# geiger.net
KiCad netlist of a schematic drawn in EAGLE
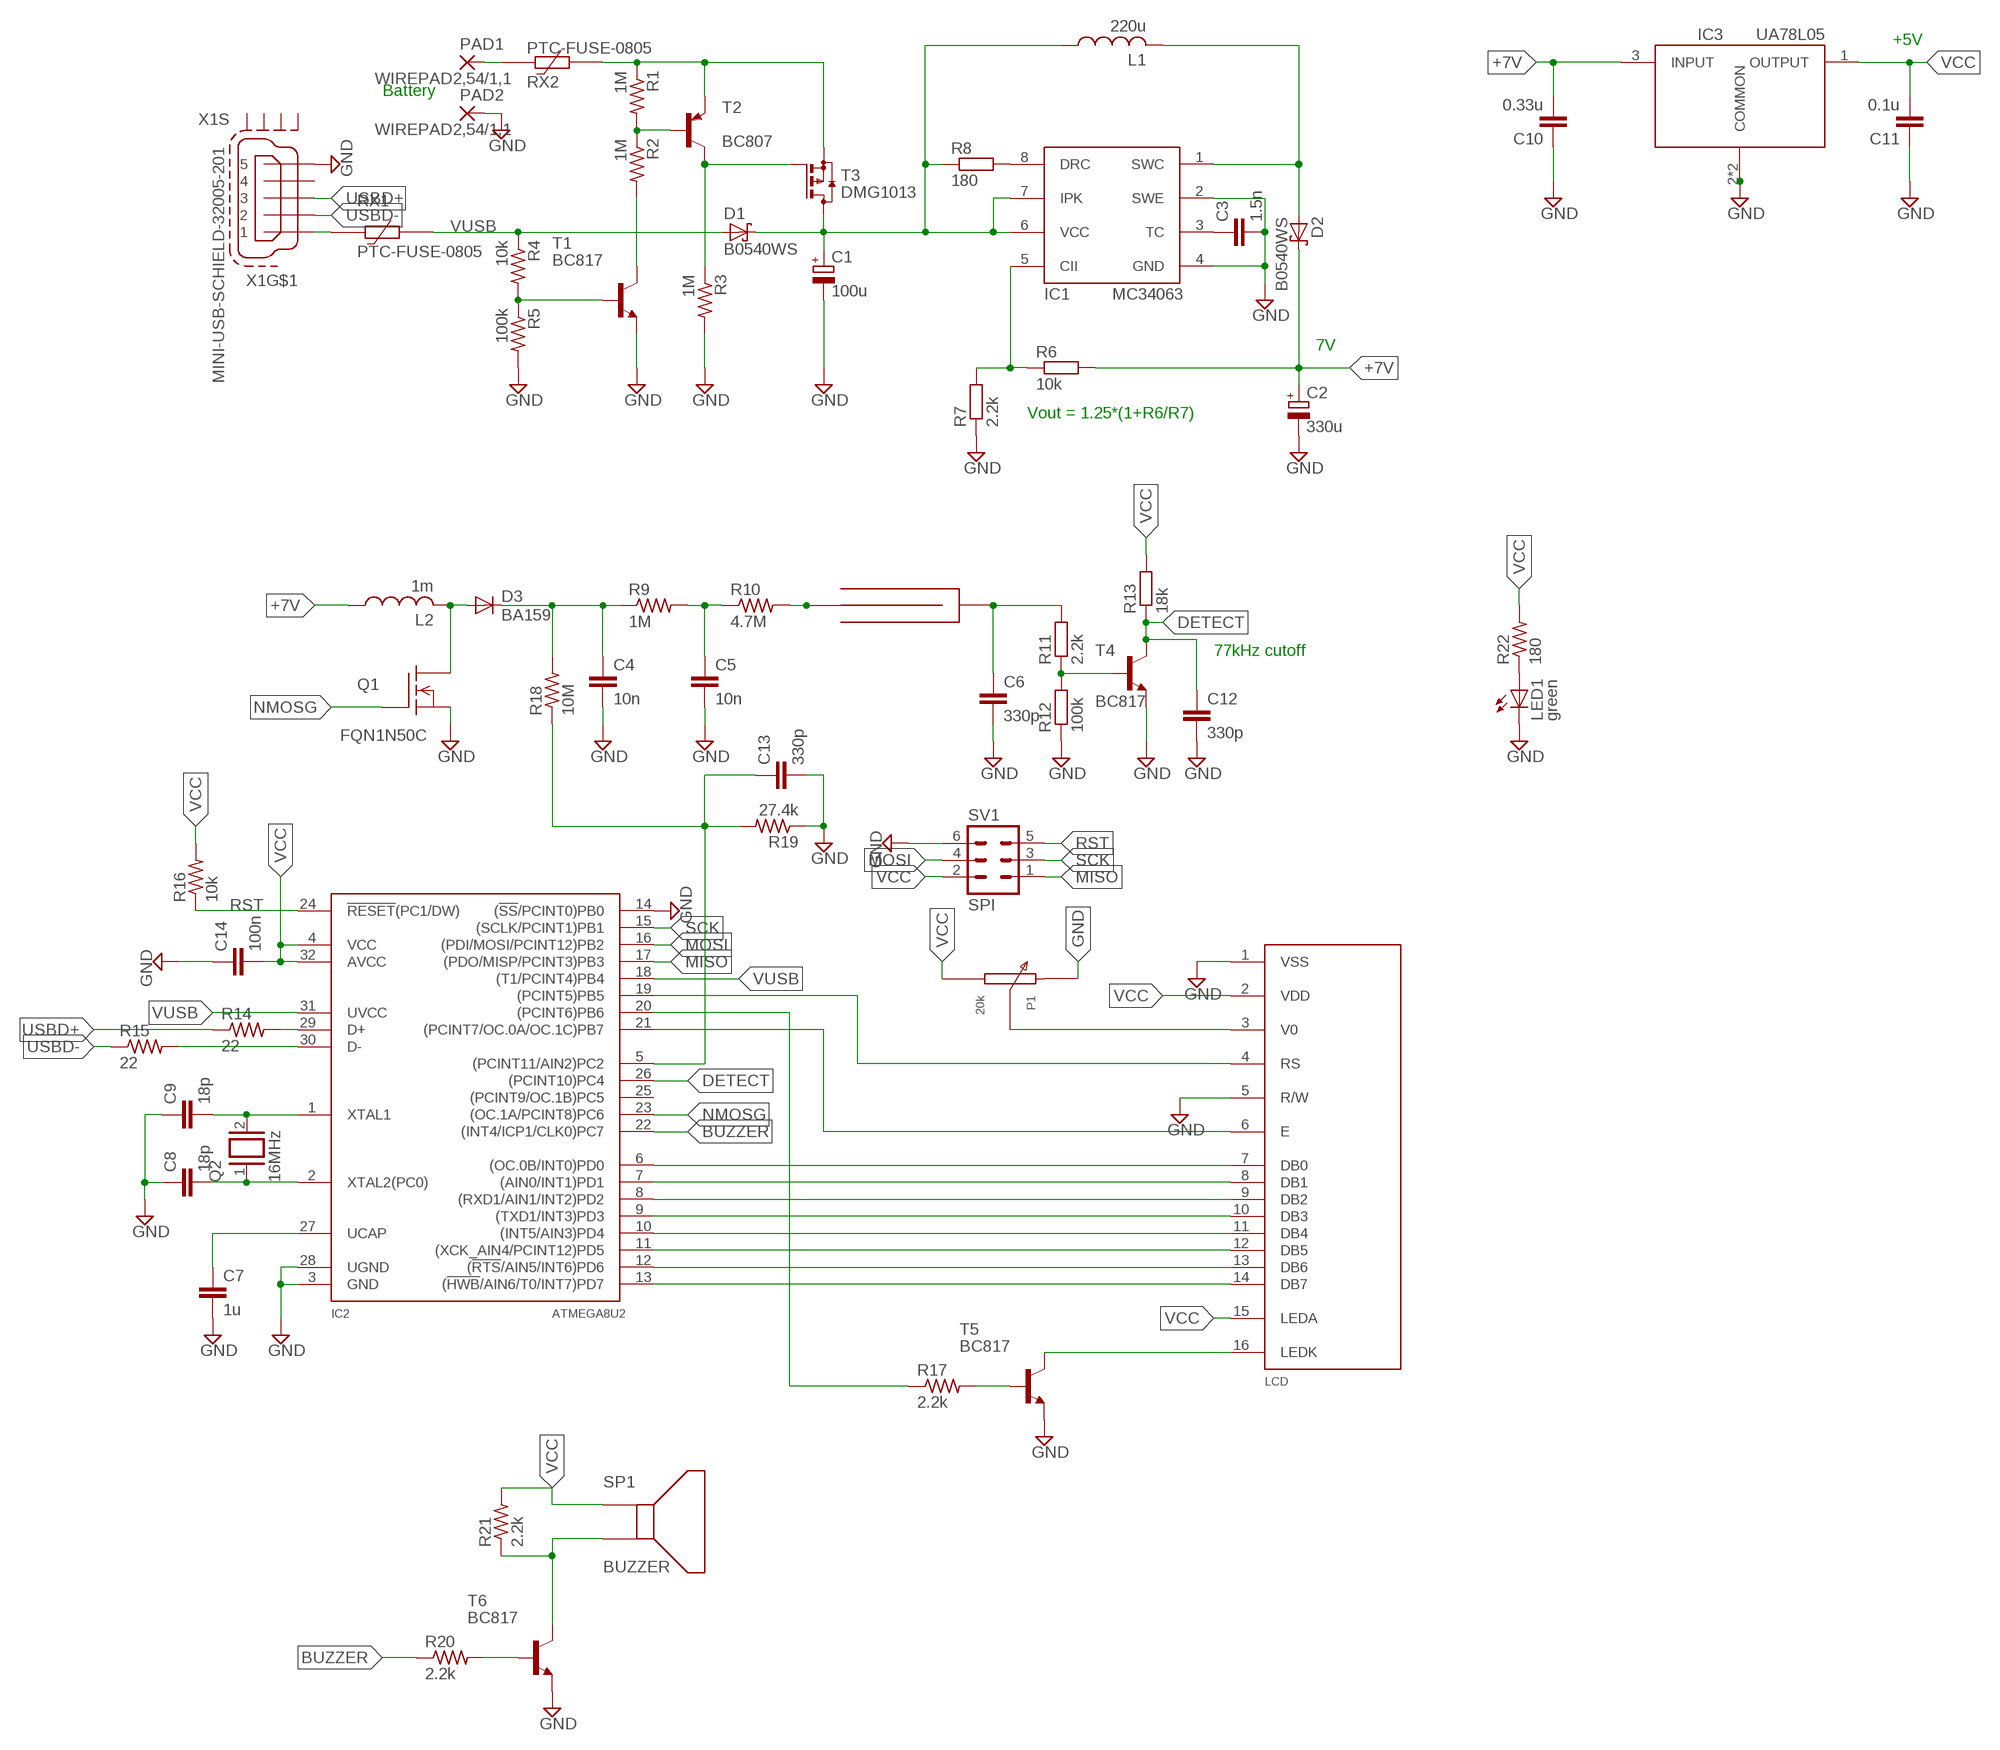
[diagram p0: schematic, sheet 1]

(export (version "E")
  (design (tool "Eeschema 10.0.6"))
  (components
    (comp (ref "C1")
      (value "100u")
      (footprint "eagle-import:E2,5-6")
      (libsource (lib "eagle-import") (part "CPOL-EUE2.5-6"))
    )
    (comp (ref "C2")
      (value "330u")
      (footprint "eagle-import:E2,5-6")
      (libsource (lib "eagle-import") (part "CPOL-EUE2.5-6"))
    )
    (comp (ref "C3")
      (value "1.5n")
      (footprint "eagle-import:C0603")
      (libsource (lib "eagle-import") (part "C-EUC0603"))
    )
    (comp (ref "C4")
      (value "10n")
      (footprint "eagle-import:C050-024X044")
      (libsource (lib "eagle-import") (part "C-EU050-024X044"))
    )
    (comp (ref "C5")
      (value "10n")
      (footprint "eagle-import:C050-024X044")
      (libsource (lib "eagle-import") (part "C-EU050-024X044"))
    )
    (comp (ref "C6")
      (value "330p")
      (footprint "eagle-import:C0603")
      (libsource (lib "eagle-import") (part "C-EUC0603"))
    )
    (comp (ref "C7")
      (value "1u")
      (footprint "eagle-import:C0603")
      (libsource (lib "eagle-import") (part "C-EUC0603"))
    )
    (comp (ref "C8")
      (value "18p")
      (footprint "eagle-import:C0603")
      (libsource (lib "eagle-import") (part "C-EUC0603"))
    )
    (comp (ref "C9")
      (value "18p")
      (footprint "eagle-import:C0603")
      (libsource (lib "eagle-import") (part "C-EUC0603"))
    )
    (comp (ref "C10")
      (value "0.33u")
      (footprint "eagle-import:C0603")
      (libsource (lib "eagle-import") (part "C-EUC0603"))
    )
    (comp (ref "C11")
      (value "0.1u")
      (footprint "eagle-import:C0603")
      (libsource (lib "eagle-import") (part "C-EUC0603"))
    )
    (comp (ref "C12")
      (value "330p")
      (footprint "eagle-import:C0603")
      (libsource (lib "eagle-import") (part "C-EUC0603"))
    )
    (comp (ref "C13")
      (value "330p")
      (footprint "eagle-import:C0603")
      (libsource (lib "eagle-import") (part "C-EUC0603"))
    )
    (comp (ref "C14")
      (value "100n")
      (footprint "eagle-import:C0603")
      (libsource (lib "eagle-import") (part "C-EUC0603"))
    )
    (comp (ref "D1")
      (value "B0540WS")
      (footprint "eagle-import:SOD323-R")
      (libsource (lib "eagle-import") (part "B0540WS"))
    )
    (comp (ref "D2")
      (value "B0540WS")
      (footprint "eagle-import:SOD323-R")
      (libsource (lib "eagle-import") (part "B0540WS"))
    )
    (comp (ref "D3")
      (value "BA159")
      (footprint "eagle-import:DO41-10")
      (libsource (lib "eagle-import") (part "BA159"))
    )
    (comp (ref "G1")
      (value "CI-22BG/SI-3BG")
      (footprint "eagle-import:FUSE102074")
      (libsource (lib "eagle-import") (part "CI-22BG/SI-3BG"))
    )
    (comp (ref "IC1")
      (value "MC34063")
      (footprint "eagle-import:SO8")
      (libsource (lib "eagle-import") (part "MC34063"))
    )
    (comp (ref "IC2")
      (value "ATMEGA8U2")
      (footprint "eagle-import:TQFP32-08")
      (libsource (lib "eagle-import") (part "ATMEGA8U2"))
    )
    (comp (ref "IC3")
      (value "UA78L05")
      (footprint "eagle-import:SOT89")
      (libsource (lib "eagle-import") (part "UA78L05"))
    )
    (comp (ref "L1")
      (value "220u")
      (footprint "eagle-import:L8012")
      (libsource (lib "eagle-import") (part "BOURNS8012"))
    )
    (comp (ref "L2")
      (value "1m")
      (footprint "eagle-import:L8012")
      (libsource (lib "eagle-import") (part "BOURNS8012"))
    )
    (comp (ref "LCD")
      (value "TAYDA-LCD")
      (footprint "eagle-import:LCD-PINOUT")
      (libsource (lib "eagle-import") (part "TAYDA-LCD"))
    )
    (comp (ref "LED1")
      (value "green")
      (footprint "eagle-import:CHIP-LED0603")
      (libsource (lib "eagle-import") (part "LEDCHIP-LED0603"))
    )
    (comp (ref "P1")
      (value "20k")
      (footprint "eagle-import:TRIMPOT")
      (libsource (lib "eagle-import") (part "TRIMPOT"))
    )
    (comp (ref "PAD1")
      (value "WIREPAD2,54/1,1")
      (footprint "eagle-import:2,54_1,1")
      (libsource (lib "eagle-import") (part "WIREPAD2,54/1,1"))
    )
    (comp (ref "PAD2")
      (value "WIREPAD2,54/1,1")
      (footprint "eagle-import:2,54_1,1")
      (libsource (lib "eagle-import") (part "WIREPAD2,54/1,1"))
    )
    (comp (ref "Q1")
      (value "FQN1N50C")
      (footprint "eagle-import:TO92")
      (libsource (lib "eagle-import") (part "FQN1N50C"))
    )
    (comp (ref "Q2")
      (value "16MHz")
      (footprint "eagle-import:QS")
      (libsource (lib "eagle-import") (part "XTAL/S"))
    )
    (comp (ref "R1")
      (value "1M")
      (footprint "eagle-import:R0603")
      (libsource (lib "eagle-import") (part "resistor_R-US_R0603"))
    )
    (comp (ref "R2")
      (value "1M")
      (footprint "eagle-import:R0603")
      (libsource (lib "eagle-import") (part "resistor_R-US_R0603"))
    )
    (comp (ref "R3")
      (value "1M")
      (footprint "eagle-import:R0603")
      (libsource (lib "eagle-import") (part "resistor_R-US_R0603"))
    )
    (comp (ref "R4")
      (value "10k")
      (footprint "eagle-import:R0603")
      (libsource (lib "eagle-import") (part "resistor_R-US_R0603"))
    )
    (comp (ref "R5")
      (value "100k")
      (footprint "eagle-import:R0603")
      (libsource (lib "eagle-import") (part "resistor_R-US_R0603"))
    )
    (comp (ref "R6")
      (value "10k")
      (footprint "eagle-import:R0603")
      (libsource (lib "eagle-import") (part "R-EU_R0603"))
    )
    (comp (ref "R7")
      (value "2.2k")
      (footprint "eagle-import:R0603")
      (libsource (lib "eagle-import") (part "R-EU_R0603"))
    )
    (comp (ref "R8")
      (value "180")
      (footprint "eagle-import:R0603")
      (libsource (lib "eagle-import") (part "R-EU_R0603"))
    )
    (comp (ref "R9")
      (value "1M")
      (footprint "eagle-import:0207_7")
      (libsource (lib "eagle-import") (part "R-US_0207/7"))
    )
    (comp (ref "R10")
      (value "4.7M")
      (footprint "eagle-import:0207_7")
      (libsource (lib "eagle-import") (part "R-US_0207/7"))
    )
    (comp (ref "R11")
      (value "2.2k")
      (footprint "eagle-import:R0603")
      (libsource (lib "eagle-import") (part "R-EU_R0603"))
    )
    (comp (ref "R12")
      (value "100k")
      (footprint "eagle-import:R0603")
      (libsource (lib "eagle-import") (part "R-EU_R0603"))
    )
    (comp (ref "R13")
      (value "18k")
      (footprint "eagle-import:R0603")
      (libsource (lib "eagle-import") (part "R-EU_R0603"))
    )
    (comp (ref "R14")
      (value "22")
      (footprint "eagle-import:R0603")
      (libsource (lib "eagle-import") (part "resistor_R-US_R0603"))
    )
    (comp (ref "R15")
      (value "22")
      (footprint "eagle-import:R0603")
      (libsource (lib "eagle-import") (part "resistor_R-US_R0603"))
    )
    (comp (ref "R16")
      (value "10k")
      (footprint "eagle-import:R0603")
      (libsource (lib "eagle-import") (part "resistor_R-US_R0603"))
    )
    (comp (ref "R17")
      (value "2.2k")
      (footprint "eagle-import:R0603")
      (libsource (lib "eagle-import") (part "resistor_R-US_R0603"))
    )
    (comp (ref "R18")
      (value "10M")
      (footprint "eagle-import:0207_7")
      (libsource (lib "eagle-import") (part "R-US_0207/7"))
    )
    (comp (ref "R19")
      (value "27.4k")
      (footprint "eagle-import:R0603")
      (libsource (lib "eagle-import") (part "resistor_R-US_R0603"))
    )
    (comp (ref "R20")
      (value "2.2k")
      (footprint "eagle-import:R0603")
      (libsource (lib "eagle-import") (part "resistor_R-US_R0603"))
    )
    (comp (ref "R21")
      (value "2.2k")
      (footprint "eagle-import:R0603")
      (libsource (lib "eagle-import") (part "resistor_R-US_R0603"))
    )
    (comp (ref "R22")
      (value "180")
      (footprint "eagle-import:R0603")
      (libsource (lib "eagle-import") (part "resistor_R-US_R0603"))
    )
    (comp (ref "RX1")
      (value "PTC-FUSE-0805")
      (footprint "eagle-import:R0805")
      (libsource (lib "eagle-import") (part "PTC-FUSE-0805"))
    )
    (comp (ref "RX2")
      (value "PTC-FUSE-0805")
      (footprint "eagle-import:R0805")
      (libsource (lib "eagle-import") (part "PTC-FUSE-0805"))
    )
    (comp (ref "SP1")
      (value "BUZZER")
      (footprint "eagle-import:BUZZER")
      (libsource (lib "eagle-import") (part "BUZZER"))
    )
    (comp (ref "SV1")
      (value "SPI")
      (footprint "eagle-import:MA03-2")
      (libsource (lib "eagle-import") (part "MA03-2"))
    )
    (comp (ref "T1")
      (value "BC817")
      (footprint "eagle-import:SOT23-BEC")
      (libsource (lib "eagle-import") (part "-NPN-SOT23-BECBC817-40"))
    )
    (comp (ref "T2")
      (value "BC807")
      (footprint "eagle-import:SOT23-BEC")
      (libsource (lib "eagle-import") (part "-PNP-SOT23-BECBC807-40"))
    )
    (comp (ref "T3")
      (value "DMG1013")
      (footprint "eagle-import:SOT323")
      (libsource (lib "eagle-import") (part "DMG1013"))
    )
    (comp (ref "T4")
      (value "BC817")
      (footprint "eagle-import:SOT23-BEC")
      (libsource (lib "eagle-import") (part "-NPN-SOT23-BECBC817-40"))
    )
    (comp (ref "T5")
      (value "BC817")
      (footprint "eagle-import:SOT23-BEC")
      (libsource (lib "eagle-import") (part "-NPN-SOT23-BECBC817-40"))
    )
    (comp (ref "T6")
      (value "BC817")
      (footprint "eagle-import:SOT23-BEC")
      (libsource (lib "eagle-import") (part "-NPN-SOT23-BECBC817-40"))
    )
    (comp (ref "X1")
      (value "MINI-USB-SCHIELD-32005-201")
      (footprint "eagle-import:32005-201")
      (libsource (lib "eagle-import") (part "MINI-USB-SCHIELD-32005-201"))
    )
  )
  (nets
    (net (code "1") (name "+7V") (class "Default")
      (node (ref "C10") (pin "2") (pinfunction "2_2") (pintype "passive"))
      (node (ref "C2") (pin "+") (pinfunction "+_+") (pintype "passive"))
      (node (ref "D2") (pin "C") (pinfunction "C_C") (pintype "passive"))
      (node (ref "IC3") (pin "3") (pinfunction "INPUT_3") (pintype "bidirectional"))
      (node (ref "L2") (pin "1") (pinfunction "1_1") (pintype "passive"))
      (node (ref "R6") (pin "2") (pinfunction "2_2") (pintype "passive"))
    )
    (net (code "2") (name "BUZZER") (class "Default")
      (node (ref "IC2") (pin "22") (pinfunction "(INT4/ICP1/CLK0)PC7_22") (pintype "bidirectional"))
      (node (ref "R20") (pin "1") (pinfunction "1_1") (pintype "passive"))
    )
    (net (code "3") (name "DETECT") (class "Default")
      (node (ref "C12") (pin "1") (pinfunction "1_1") (pintype "passive"))
      (node (ref "IC2") (pin "26") (pinfunction "(PCINT10)PC4_26") (pintype "bidirectional"))
      (node (ref "R13") (pin "1") (pinfunction "1_1") (pintype "passive"))
      (node (ref "T4") (pin "C") (pinfunction "C_C") (pintype "passive"))
    )
    (net (code "4") (name "GND") (class "Default")
      (node (ref "C1") (pin "-") (pinfunction "-_-") (pintype "passive"))
      (node (ref "C10") (pin "1") (pinfunction "1_1") (pintype "passive"))
      (node (ref "C11") (pin "1") (pinfunction "1_1") (pintype "passive"))
      (node (ref "C12") (pin "2") (pinfunction "2_2") (pintype "passive"))
      (node (ref "C13") (pin "2") (pinfunction "2_2") (pintype "passive"))
      (node (ref "C14") (pin "1") (pinfunction "1_1") (pintype "passive"))
      (node (ref "C2") (pin "-") (pinfunction "-_-") (pintype "passive"))
      (node (ref "C3") (pin "2") (pinfunction "2_2") (pintype "passive"))
      (node (ref "C4") (pin "2") (pinfunction "2_2") (pintype "passive"))
      (node (ref "C5") (pin "2") (pinfunction "2_2") (pintype "passive"))
      (node (ref "C6") (pin "2") (pinfunction "2_2") (pintype "passive"))
      (node (ref "C7") (pin "2") (pinfunction "2_2") (pintype "passive"))
      (node (ref "C8") (pin "1") (pinfunction "1_1") (pintype "passive"))
      (node (ref "C9") (pin "1") (pinfunction "1_1") (pintype "passive"))
      (node (ref "IC1") (pin "2") (pinfunction "SWE_2") (pintype "bidirectional"))
      (node (ref "IC1") (pin "4") (pinfunction "GND_4") (pintype "bidirectional"))
      (node (ref "IC2") (pin "14") (pinfunction "(~{SS}/PCINT0)PB0_14") (pintype "bidirectional"))
      (node (ref "IC2") (pin "28") (pinfunction "UGND_28") (pintype "bidirectional"))
      (node (ref "IC2") (pin "3") (pinfunction "GND_3") (pintype "bidirectional"))
      (node (ref "IC3") (pin "2") (pinfunction "COMMON_2") (pintype "bidirectional"))
      (node (ref "IC3") (pin "2@1") (pinfunction "COMMON_2@1") (pintype "bidirectional"))
      (node (ref "LCD") (pin "1") (pinfunction "VSS_1") (pintype "bidirectional"))
      (node (ref "LCD") (pin "5") (pinfunction "R/W_5") (pintype "bidirectional"))
      (node (ref "LED1") (pin "C") (pinfunction "C_C") (pintype "passive"))
      (node (ref "P1") (pin "P$2") (pinfunction "1_P$2") (pintype "bidirectional"))
      (node (ref "PAD2") (pin "1") (pinfunction "P_1") (pintype "passive"))
      (node (ref "Q1") (pin "1") (pinfunction "S_1") (pintype "passive"))
      (node (ref "R12") (pin "1") (pinfunction "1_1") (pintype "passive"))
      (node (ref "R19") (pin "1") (pinfunction "1_1") (pintype "passive"))
      (node (ref "R3") (pin "2") (pinfunction "2_2") (pintype "passive"))
      (node (ref "R5") (pin "2") (pinfunction "2_2") (pintype "passive"))
      (node (ref "R7") (pin "1") (pinfunction "1_1") (pintype "passive"))
      (node (ref "SV1") (pin "6") (pinfunction "6_6") (pintype "passive"))
      (node (ref "T1") (pin "E") (pinfunction "E_E") (pintype "passive"))
      (node (ref "T4") (pin "E") (pinfunction "E_E") (pintype "passive"))
      (node (ref "T5") (pin "E") (pinfunction "E_E") (pintype "passive"))
      (node (ref "T6") (pin "E") (pinfunction "E_E") (pintype "passive"))
      (node (ref "X1") (pin "5") (pinfunction "5_5") (pintype "passive"))
    )
    (net (code "5") (name "MISO") (class "Default")
      (node (ref "IC2") (pin "17") (pinfunction "(PDO/MISP/PCINT3)PB3_17") (pintype "bidirectional"))
      (node (ref "SV1") (pin "1") (pinfunction "1_1") (pintype "passive"))
    )
    (net (code "6") (name "MOSI") (class "Default")
      (node (ref "IC2") (pin "16") (pinfunction "(PDI/MOSI/PCINT12)PB2_16") (pintype "bidirectional"))
      (node (ref "SV1") (pin "4") (pinfunction "4_4") (pintype "passive"))
    )
    (net (code "7") (name "NMOSG") (class "Default")
      (node (ref "IC2") (pin "23") (pinfunction "(OC.1A/PCINT8)PC6_23") (pintype "bidirectional"))
      (node (ref "Q1") (pin "3") (pinfunction "G_3") (pintype "passive"))
    )
    (net (code "8") (name "Net-(C4-Pad1)") (class "Default")
      (node (ref "C4") (pin "1") (pinfunction "1_1") (pintype "passive"))
      (node (ref "D3") (pin "C") (pinfunction "C_C") (pintype "passive"))
      (node (ref "R18") (pin "2") (pinfunction "2_2") (pintype "passive"))
      (node (ref "R9") (pin "1") (pinfunction "1_1") (pintype "passive"))
    )
    (net (code "9") (name "Net-(C5-Pad1)") (class "Default")
      (node (ref "C5") (pin "1") (pinfunction "1_1") (pintype "passive"))
      (node (ref "R10") (pin "1") (pinfunction "1_1") (pintype "passive"))
      (node (ref "R9") (pin "2") (pinfunction "2_2") (pintype "passive"))
    )
    (net (code "10") (name "Net-(C6-Pad1)") (class "Default")
      (node (ref "C6") (pin "1") (pinfunction "1_1") (pintype "passive"))
      (node (ref "G1") (pin "C1") (pinfunction "C_C1") (pintype "bidirectional"))
      (node (ref "G1") (pin "C2") (pinfunction "C_C2") (pintype "bidirectional"))
      (node (ref "G1") (pin "C3") (pinfunction "C_C3") (pintype "bidirectional"))
      (node (ref "G1") (pin "C4") (pinfunction "C_C4") (pintype "bidirectional"))
      (node (ref "R11") (pin "2") (pinfunction "2_2") (pintype "passive"))
    )
    (net (code "11") (name "Net-(G1-A-PadA1)") (class "Default")
      (node (ref "G1") (pin "A1") (pinfunction "A_A1") (pintype "bidirectional"))
      (node (ref "G1") (pin "A2") (pinfunction "A_A2") (pintype "bidirectional"))
      (node (ref "R10") (pin "2") (pinfunction "2_2") (pintype "passive"))
    )
    (net (code "12") (name "Net-(IC1-CII)") (class "Default")
      (node (ref "IC1") (pin "5") (pinfunction "CII_5") (pintype "bidirectional"))
      (node (ref "R6") (pin "1") (pinfunction "1_1") (pintype "passive"))
      (node (ref "R7") (pin "2") (pinfunction "2_2") (pintype "passive"))
    )
    (net (code "13") (name "Net-(IC1-DRC)") (class "Default")
      (node (ref "IC1") (pin "8") (pinfunction "DRC_8") (pintype "bidirectional"))
      (node (ref "R8") (pin "2") (pinfunction "2_2") (pintype "passive"))
    )
    (net (code "14") (name "Net-(IC1-IPK)") (class "Default")
      (node (ref "C1") (pin "+") (pinfunction "+_+") (pintype "passive"))
      (node (ref "D1") (pin "C") (pinfunction "C_C") (pintype "passive"))
      (node (ref "IC1") (pin "6") (pinfunction "VCC_6") (pintype "bidirectional"))
      (node (ref "IC1") (pin "7") (pinfunction "IPK_7") (pintype "bidirectional"))
      (node (ref "L1") (pin "1") (pinfunction "1_1") (pintype "passive"))
      (node (ref "R8") (pin "1") (pinfunction "1_1") (pintype "passive"))
      (node (ref "T3") (pin "1") (pinfunction "D_1") (pintype "passive"))
    )
    (net (code "15") (name "Net-(IC1-SWC)") (class "Default")
      (node (ref "D2") (pin "A") (pinfunction "A_A") (pintype "passive"))
      (node (ref "IC1") (pin "1") (pinfunction "SWC_1") (pintype "bidirectional"))
      (node (ref "L1") (pin "2") (pinfunction "2_2") (pintype "passive"))
    )
    (net (code "16") (name "Net-(IC1-TC)") (class "Default")
      (node (ref "C3") (pin "1") (pinfunction "1_1") (pintype "passive"))
      (node (ref "IC1") (pin "3") (pinfunction "TC_3") (pintype "bidirectional"))
    )
    (net (code "17") (name "Net-(IC2-(AIN0{slash}INT1)PD1)") (class "Default")
      (node (ref "IC2") (pin "7") (pinfunction "(AIN0/INT1)PD1_7") (pintype "bidirectional"))
      (node (ref "LCD") (pin "8") (pinfunction "DB1_8") (pintype "bidirectional"))
    )
    (net (code "18") (name "Net-(IC2-(INT5{slash}AIN3)PD4)") (class "Default")
      (node (ref "IC2") (pin "10") (pinfunction "(INT5/AIN3)PD4_10") (pintype "bidirectional"))
      (node (ref "LCD") (pin "11") (pinfunction "DB4_11") (pintype "bidirectional"))
    )
    (net (code "19") (name "Net-(IC2-(OC.0B{slash}INT0)PD0)") (class "Default")
      (node (ref "IC2") (pin "6") (pinfunction "(OC.0B/INT0)PD0_6") (pintype "bidirectional"))
      (node (ref "LCD") (pin "7") (pinfunction "DB0_7") (pintype "bidirectional"))
    )
    (net (code "20") (name "Net-(IC2-(PCINT5)PB5)") (class "Default")
      (node (ref "IC2") (pin "19") (pinfunction "(PCINT5)PB5_19") (pintype "bidirectional"))
      (node (ref "LCD") (pin "4") (pinfunction "RS_4") (pintype "bidirectional"))
    )
    (net (code "21") (name "Net-(IC2-(PCINT6)PB6)") (class "Default")
      (node (ref "IC2") (pin "20") (pinfunction "(PCINT6)PB6_20") (pintype "bidirectional"))
      (node (ref "R17") (pin "1") (pinfunction "1_1") (pintype "passive"))
    )
    (net (code "22") (name "Net-(IC2-(PCINT7{slash}OC.0A{slash}OC.1C)PB7)") (class "Default")
      (node (ref "IC2") (pin "21") (pinfunction "(PCINT7/OC.0A/OC.1C)PB7_21") (pintype "bidirectional"))
      (node (ref "LCD") (pin "6") (pinfunction "E_6") (pintype "bidirectional"))
    )
    (net (code "23") (name "Net-(IC2-(PCINT11{slash}AIN2)PC2)") (class "Default")
      (node (ref "C13") (pin "1") (pinfunction "1_1") (pintype "passive"))
      (node (ref "IC2") (pin "5") (pinfunction "(PCINT11/AIN2)PC2_5") (pintype "bidirectional"))
      (node (ref "R18") (pin "1") (pinfunction "1_1") (pintype "passive"))
      (node (ref "R19") (pin "2") (pinfunction "2_2") (pintype "passive"))
    )
    (net (code "24") (name "Net-(IC2-(RXD1{slash}AIN1{slash}INT2)PD2)") (class "Default")
      (node (ref "IC2") (pin "8") (pinfunction "(RXD1/AIN1/INT2)PD2_8") (pintype "bidirectional"))
      (node (ref "LCD") (pin "9") (pinfunction "DB2_9") (pintype "bidirectional"))
    )
    (net (code "25") (name "Net-(IC2-(TXD1{slash}INT3)PD3)") (class "Default")
      (node (ref "IC2") (pin "9") (pinfunction "(TXD1/INT3)PD3_9") (pintype "bidirectional"))
      (node (ref "LCD") (pin "10") (pinfunction "DB3_10") (pintype "bidirectional"))
    )
    (net (code "26") (name "Net-(IC2-(XCK_AIN4{slash}PCINT12)PD5)") (class "Default")
      (node (ref "IC2") (pin "11") (pinfunction "(XCK_AIN4/PCINT12)PD5_11") (pintype "bidirectional"))
      (node (ref "LCD") (pin "12") (pinfunction "DB5_12") (pintype "bidirectional"))
    )
    (net (code "27") (name "Net-(IC2-(~{HWB}{slash}AIN6{slash}T0{slash}INT7)PD7)") (class "Default")
      (node (ref "IC2") (pin "13") (pinfunction "(~{HWB}/AIN6/T0/INT7)PD7_13") (pintype "bidirectional"))
      (node (ref "LCD") (pin "14") (pinfunction "DB7_14") (pintype "bidirectional"))
    )
    (net (code "28") (name "Net-(IC2-(~{RTS}{slash}AIN5{slash}INT6)PD6)") (class "Default")
      (node (ref "IC2") (pin "12") (pinfunction "(~{RTS}/AIN5/INT6)PD6_12") (pintype "bidirectional"))
      (node (ref "LCD") (pin "13") (pinfunction "DB6_13") (pintype "bidirectional"))
    )
    (net (code "29") (name "Net-(IC2-D+)") (class "Default")
      (node (ref "IC2") (pin "29") (pinfunction "D+_29") (pintype "bidirectional"))
      (node (ref "R14") (pin "2") (pinfunction "2_2") (pintype "passive"))
    )
    (net (code "30") (name "Net-(IC2-D-)") (class "Default")
      (node (ref "IC2") (pin "30") (pinfunction "D-_30") (pintype "bidirectional"))
      (node (ref "R15") (pin "2") (pinfunction "2_2") (pintype "passive"))
    )
    (net (code "31") (name "Net-(IC2-UCAP)") (class "Default")
      (node (ref "C7") (pin "1") (pinfunction "1_1") (pintype "passive"))
      (node (ref "IC2") (pin "27") (pinfunction "UCAP_27") (pintype "bidirectional"))
    )
    (net (code "32") (name "Net-(IC2-XTAL1)") (class "Default")
      (node (ref "C9") (pin "2") (pinfunction "2_2") (pintype "passive"))
      (node (ref "IC2") (pin "1") (pinfunction "XTAL1_1") (pintype "bidirectional"))
      (node (ref "Q2") (pin "2") (pinfunction "2_2") (pintype "passive"))
    )
    (net (code "33") (name "Net-(IC2-XTAL2(PC0))") (class "Default")
      (node (ref "C8") (pin "2") (pinfunction "2_2") (pintype "passive"))
      (node (ref "IC2") (pin "2") (pinfunction "XTAL2(PC0)_2") (pintype "bidirectional"))
      (node (ref "Q2") (pin "1") (pinfunction "1_1") (pintype "passive"))
    )
    (net (code "34") (name "Net-(LCD-LEDK)") (class "Default")
      (node (ref "LCD") (pin "16") (pinfunction "LEDK_16") (pintype "bidirectional"))
      (node (ref "T5") (pin "C") (pinfunction "C_C") (pintype "passive"))
    )
    (net (code "35") (name "Net-(LCD-V0)") (class "Default")
      (node (ref "LCD") (pin "3") (pinfunction "V0_3") (pintype "bidirectional"))
      (node (ref "P1") (pin "P$1") (pinfunction "WIPER_P$1") (pintype "bidirectional"))
    )
    (net (code "36") (name "Net-(LED1-PadA)") (class "Default")
      (node (ref "LED1") (pin "A") (pinfunction "A_A") (pintype "passive"))
      (node (ref "R22") (pin "1") (pinfunction "1_1") (pintype "passive"))
    )
    (net (code "37") (name "Net-(PAD1-P)") (class "Default")
      (node (ref "PAD1") (pin "1") (pinfunction "P_1") (pintype "passive"))
      (node (ref "RX2") (pin "1") (pinfunction "P$1_1") (pintype "bidirectional"))
    )
    (net (code "38") (name "Net-(Q1-D)") (class "Default")
      (node (ref "D3") (pin "A") (pinfunction "A_A") (pintype "passive"))
      (node (ref "L2") (pin "2") (pinfunction "2_2") (pintype "passive"))
      (node (ref "Q1") (pin "2") (pinfunction "D_2") (pintype "passive"))
    )
    (net (code "39") (name "Net-(R1-Pad2)") (class "Default")
      (node (ref "R1") (pin "2") (pinfunction "2_2") (pintype "passive"))
      (node (ref "R2") (pin "1") (pinfunction "1_1") (pintype "passive"))
      (node (ref "T2") (pin "B") (pinfunction "B_B") (pintype "passive"))
    )
    (net (code "40") (name "Net-(R2-Pad2)") (class "Default")
      (node (ref "R2") (pin "2") (pinfunction "2_2") (pintype "passive"))
      (node (ref "T1") (pin "C") (pinfunction "C_C") (pintype "passive"))
    )
    (net (code "41") (name "Net-(R4-Pad2)") (class "Default")
      (node (ref "R4") (pin "2") (pinfunction "2_2") (pintype "passive"))
      (node (ref "R5") (pin "1") (pinfunction "1_1") (pintype "passive"))
      (node (ref "T1") (pin "B") (pinfunction "B_B") (pintype "passive"))
    )
    (net (code "42") (name "Net-(R11-Pad1)") (class "Default")
      (node (ref "R11") (pin "1") (pinfunction "1_1") (pintype "passive"))
      (node (ref "R12") (pin "2") (pinfunction "2_2") (pintype "passive"))
      (node (ref "T4") (pin "B") (pinfunction "B_B") (pintype "passive"))
    )
    (net (code "43") (name "Net-(R17-Pad2)") (class "Default")
      (node (ref "R17") (pin "2") (pinfunction "2_2") (pintype "passive"))
      (node (ref "T5") (pin "B") (pinfunction "B_B") (pintype "passive"))
    )
    (net (code "44") (name "Net-(R20-Pad2)") (class "Default")
      (node (ref "R20") (pin "2") (pinfunction "2_2") (pintype "passive"))
      (node (ref "T6") (pin "B") (pinfunction "B_B") (pintype "passive"))
    )
    (net (code "45") (name "Net-(R21-Pad1)") (class "Default")
      (node (ref "R21") (pin "1") (pinfunction "1_1") (pintype "passive"))
      (node (ref "SP1") (pin "P$2") (pinfunction "P$2_P$2") (pintype "bidirectional"))
      (node (ref "T6") (pin "C") (pinfunction "C_C") (pintype "passive"))
    )
    (net (code "46") (name "Net-(RX1-P$1)") (class "Default")
      (node (ref "RX1") (pin "1") (pinfunction "P$1_1") (pintype "bidirectional"))
      (node (ref "X1") (pin "1") (pinfunction "1_1") (pintype "passive"))
    )
    (net (code "47") (name "Net-(RX2-P$2)") (class "Default")
      (node (ref "R1") (pin "1") (pinfunction "1_1") (pintype "passive"))
      (node (ref "RX2") (pin "2") (pinfunction "P$2_2") (pintype "bidirectional"))
      (node (ref "T2") (pin "E") (pinfunction "E_E") (pintype "passive"))
      (node (ref "T3") (pin "3") (pinfunction "S_3") (pintype "passive"))
    )
    (net (code "48") (name "Net-(T3-G)") (class "Default")
      (node (ref "R3") (pin "1") (pinfunction "1_1") (pintype "passive"))
      (node (ref "T2") (pin "C") (pinfunction "C_C") (pintype "passive"))
      (node (ref "T3") (pin "2") (pinfunction "G_2") (pintype "passive"))
    )
    (net (code "49") (name "RST") (class "Default")
      (node (ref "IC2") (pin "24") (pinfunction "~{RESET}(PC1/DW)_24") (pintype "bidirectional"))
      (node (ref "R16") (pin "1") (pinfunction "1_1") (pintype "passive"))
      (node (ref "SV1") (pin "5") (pinfunction "5_5") (pintype "passive"))
    )
    (net (code "50") (name "SCK") (class "Default")
      (node (ref "IC2") (pin "15") (pinfunction "(SCLK/PCINT1)PB1_15") (pintype "bidirectional"))
      (node (ref "SV1") (pin "3") (pinfunction "3_3") (pintype "passive"))
    )
    (net (code "51") (name "USBD+") (class "Default")
      (node (ref "R14") (pin "1") (pinfunction "1_1") (pintype "passive"))
      (node (ref "X1") (pin "3") (pinfunction "3_3") (pintype "passive"))
    )
    (net (code "52") (name "USBD-") (class "Default")
      (node (ref "R15") (pin "1") (pinfunction "1_1") (pintype "passive"))
      (node (ref "X1") (pin "2") (pinfunction "2_2") (pintype "passive"))
    )
    (net (code "53") (name "VCC") (class "Default")
      (node (ref "C11") (pin "2") (pinfunction "2_2") (pintype "passive"))
      (node (ref "C14") (pin "2") (pinfunction "2_2") (pintype "passive"))
      (node (ref "IC2") (pin "32") (pinfunction "AVCC_32") (pintype "bidirectional"))
      (node (ref "IC2") (pin "4") (pinfunction "VCC_4") (pintype "bidirectional"))
      (node (ref "IC3") (pin "1") (pinfunction "OUTPUT_1") (pintype "bidirectional"))
      (node (ref "LCD") (pin "15") (pinfunction "LEDA_15") (pintype "bidirectional"))
      (node (ref "LCD") (pin "2") (pinfunction "VDD_2") (pintype "bidirectional"))
      (node (ref "P1") (pin "P$3") (pinfunction "2_P$3") (pintype "bidirectional"))
      (node (ref "R13") (pin "2") (pinfunction "2_2") (pintype "passive"))
      (node (ref "R16") (pin "2") (pinfunction "2_2") (pintype "passive"))
      (node (ref "R21") (pin "2") (pinfunction "2_2") (pintype "passive"))
      (node (ref "R22") (pin "2") (pinfunction "2_2") (pintype "passive"))
      (node (ref "SP1") (pin "P$1") (pinfunction "P$1_P$1") (pintype "bidirectional"))
      (node (ref "SV1") (pin "2") (pinfunction "2_2") (pintype "passive"))
    )
    (net (code "54") (name "VUSB") (class "Default")
      (node (ref "D1") (pin "A") (pinfunction "A_A") (pintype "passive"))
      (node (ref "IC2") (pin "18") (pinfunction "(T1/PCINT4)PB4_18") (pintype "bidirectional"))
      (node (ref "IC2") (pin "31") (pinfunction "UVCC_31") (pintype "bidirectional"))
      (node (ref "R4") (pin "1") (pinfunction "1_1") (pintype "passive"))
      (node (ref "RX1") (pin "2") (pinfunction "P$2_2") (pintype "bidirectional"))
    )
    (net (code "55") (name "unconnected-(IC2-(PCINT9{slash}OC.1B)PC5-Pad25)") (class "Default")
      (node (ref "IC2") (pin "25") (pinfunction "(PCINT9/OC.1B)PC5_25") (pintype "bidirectional"))
    )
    (net (code "56") (name "unconnected-(X1-Pad4)") (class "Default")
      (node (ref "X1") (pin "4") (pinfunction "4_4") (pintype "passive"))
    )
    (net (code "57") (name "unconnected-(X1B-S1-PadM1)") (class "Default")
      (node (ref "X1") (pin "M1") (pinfunction "S1_M1") (pintype "passive"))
    )
    (net (code "58") (name "unconnected-(X1B-S2-PadM2)") (class "Default")
      (node (ref "X1") (pin "M2") (pinfunction "S2_M2") (pintype "passive"))
    )
    (net (code "59") (name "unconnected-(X1B-S3-PadM3)") (class "Default")
      (node (ref "X1") (pin "M3") (pinfunction "S3_M3") (pintype "passive"))
    )
    (net (code "60") (name "unconnected-(X1B-S4-PadM4)") (class "Default")
      (node (ref "X1") (pin "M4") (pinfunction "S4_M4") (pintype "passive"))
    )
  )
)
